# Adafruit_Trinket_3_3V.net
KiCad netlist of a schematic drawn in EAGLE
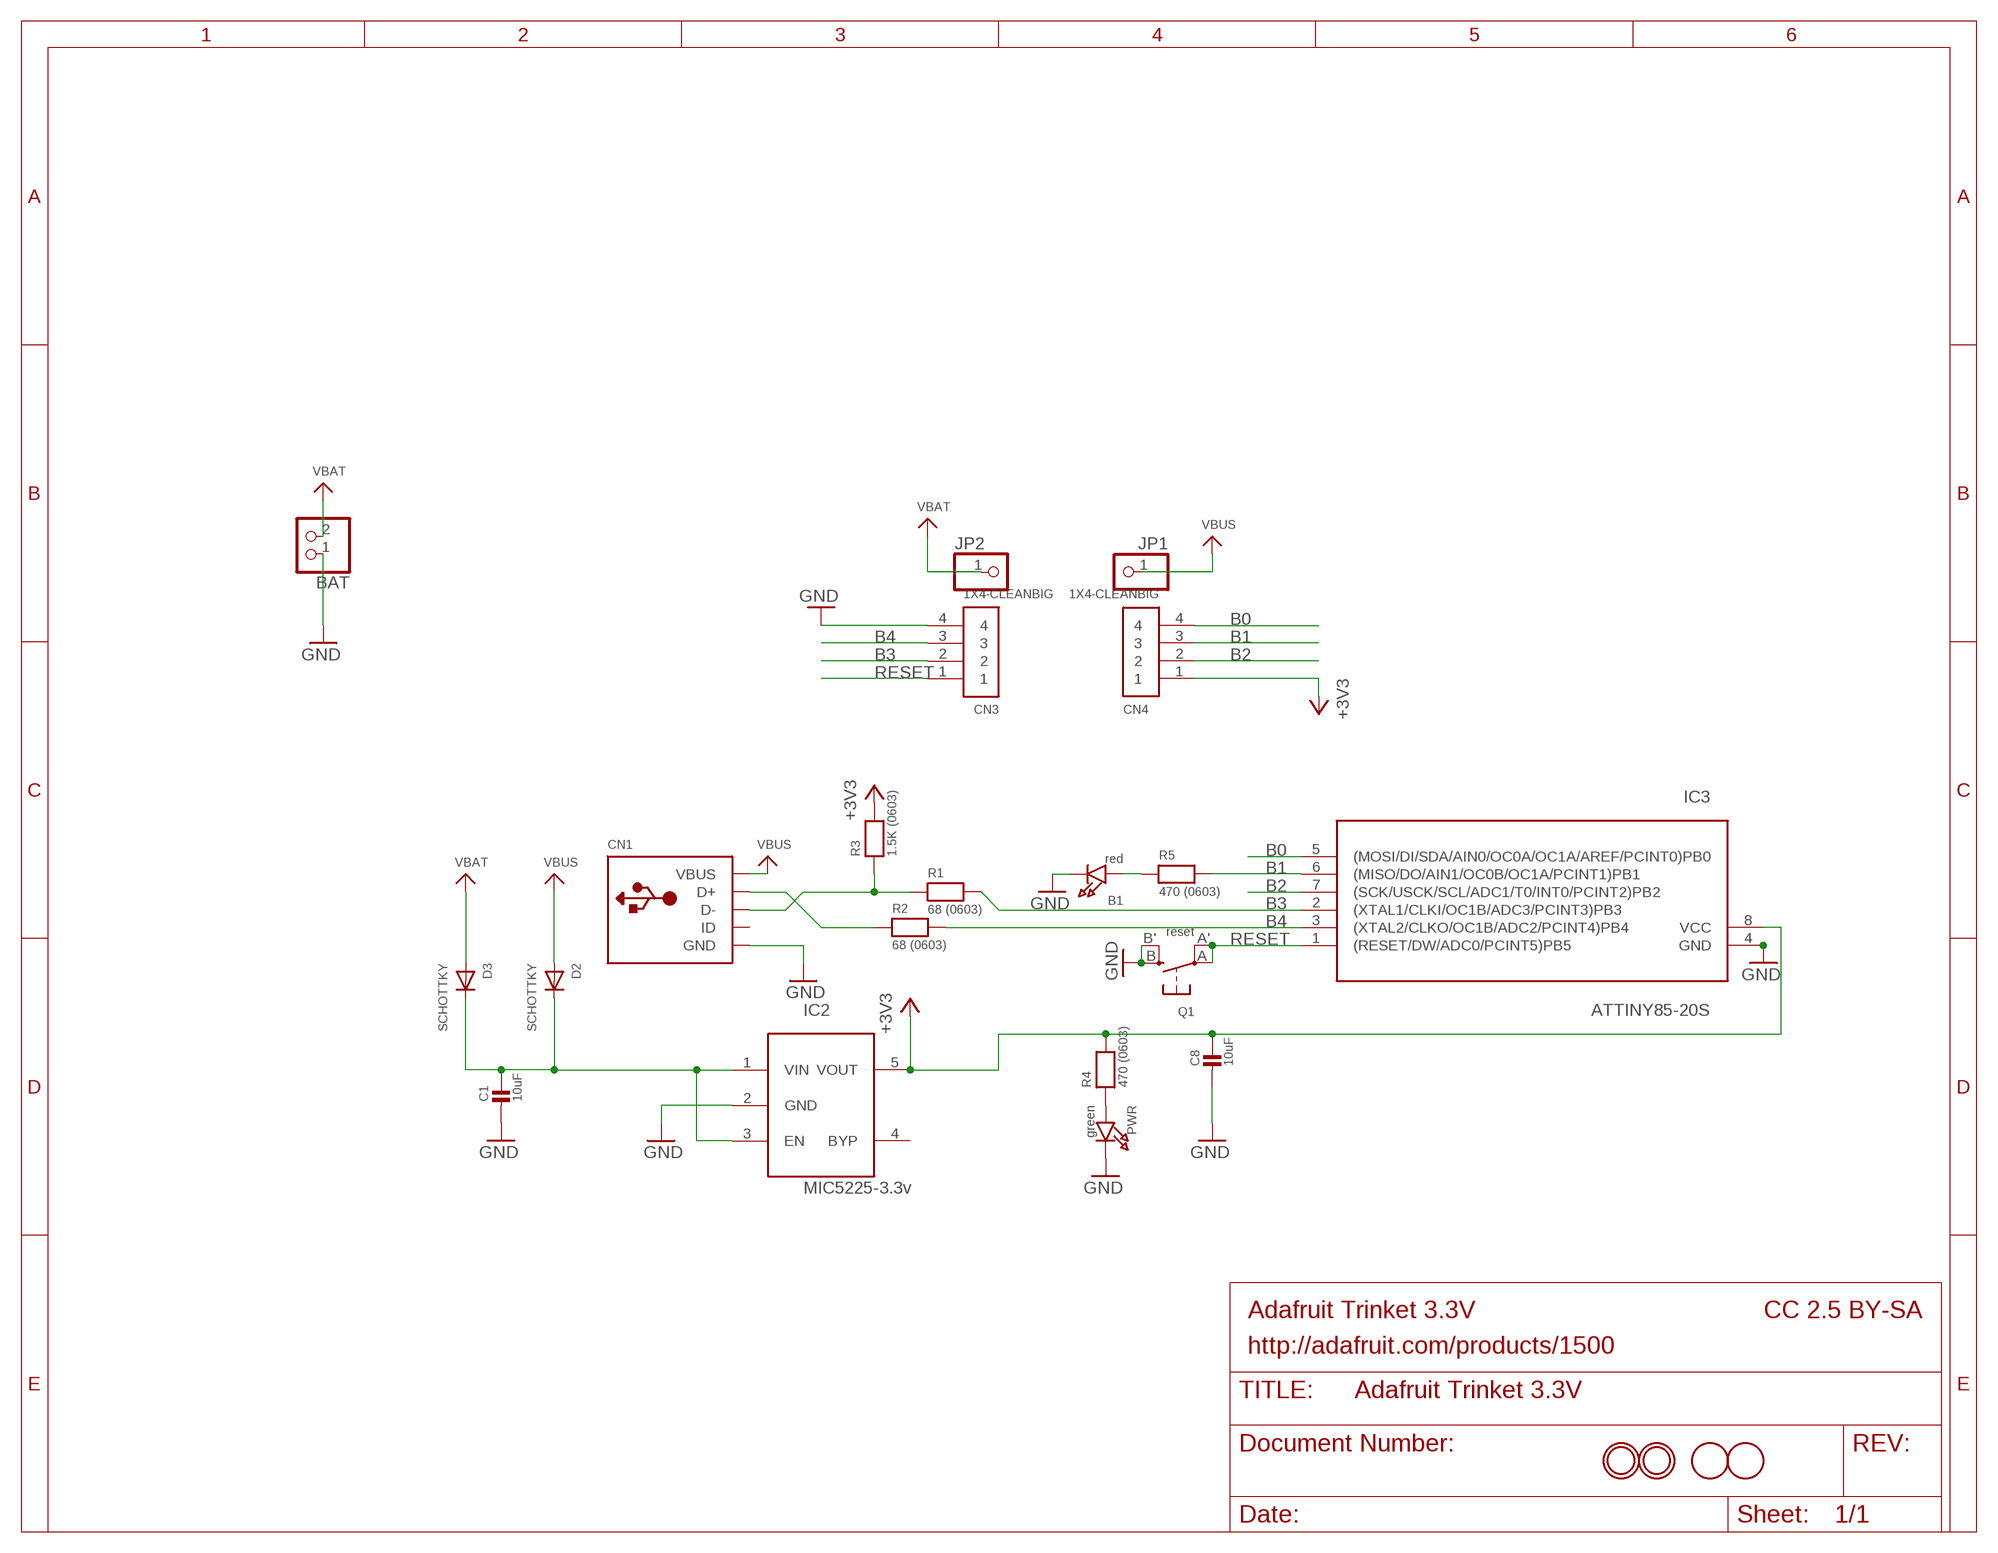
[diagram p0: schematic, sheet 1]

(export (version "E")
  (design (tool "Eeschema 10.0.6"))
  (components
    (comp (ref "B1")
      (value "red")
      (footprint "eagle-import:CHIPLED_0805_NOOUTLINE")
      (libsource (lib "eagle-import") (part "LED0805_NOOUTLINE"))
    )
    (comp (ref "BAT")
      (value "CON_JST_PH_2PIN")
      (footprint "eagle-import:JSTPH2")
      (libsource (lib "eagle-import") (part "CON_JST_PH_2PIN"))
    )
    (comp (ref "C1")
      (value "10uF")
      (footprint "eagle-import:0805-NO")
      (libsource (lib "eagle-import") (part "CAP_CERAMIC0805-NOOUTLINE"))
    )
    (comp (ref "C8")
      (value "10uF")
      (footprint "eagle-import:0805-NO")
      (libsource (lib "eagle-import") (part "CAP_CERAMIC0805-NOOUTLINE"))
    )
    (comp (ref "CN1")
      (value "USBMINIB")
      (footprint "eagle-import:USB-MINIB")
      (libsource (lib "eagle-import") (part "USBMINIB"))
    )
    (comp (ref "CN3")
      (value "1X4-CLEANBIG")
      (footprint "eagle-import:1X04-CLEANBIG")
      (libsource (lib "eagle-import") (part "1X4-CLEANBIG"))
    )
    (comp (ref "CN4")
      (value "1X4-CLEANBIG")
      (footprint "eagle-import:1X04-CLEANBIG")
      (libsource (lib "eagle-import") (part "1X4-CLEANBIG"))
    )
    (comp (ref "D2")
      (value "SCHOTTKY")
      (footprint "eagle-import:SOD-123FL")
      (libsource (lib "eagle-import") (part "DIODE_SOD-123FL"))
    )
    (comp (ref "D3")
      (value "SCHOTTKY")
      (footprint "eagle-import:SOD-123FL")
      (libsource (lib "eagle-import") (part "DIODE_SOD-123FL"))
    )
    (comp (ref "IC2")
      (value "MIC5225-3.3v")
      (footprint "eagle-import:SOT23-5L")
      (libsource (lib "eagle-import") (part "LP298XS"))
    )
    (comp (ref "IC3")
      (value "ATTINY85-20S")
      (footprint "eagle-import:SOIC8")
      (libsource (lib "eagle-import") (part "ATTINY85SV-10"))
    )
    (comp (ref "JP1")
      (value "PINHD-1X1CB")
      (footprint "eagle-import:1X01-CLEANBIG")
      (libsource (lib "eagle-import") (part "PINHD-1X1CB"))
    )
    (comp (ref "JP2")
      (value "PINHD-1X1CB")
      (footprint "eagle-import:1X01-CLEANBIG")
      (libsource (lib "eagle-import") (part "PINHD-1X1CB"))
    )
    (comp (ref "PWR")
      (value "green")
      (footprint "eagle-import:CHIPLED_0805_NOOUTLINE")
      (libsource (lib "eagle-import") (part "LED0805_NOOUTLINE"))
    )
    (comp (ref "Q1")
      (value "reset")
      (footprint "eagle-import:BTN_KMR2_4.6X2.8")
      (libsource (lib "eagle-import") (part "SWITCH_TACT_SMT4.6X2.8"))
    )
    (comp (ref "R1")
      (value "68 (0603)")
      (footprint "eagle-import:0603-NO")
      (libsource (lib "eagle-import") (part "RESISTOR_0603_NOOUT"))
    )
    (comp (ref "R2")
      (value "68 (0603)")
      (footprint "eagle-import:0603-NO")
      (libsource (lib "eagle-import") (part "RESISTOR_0603_NOOUT"))
    )
    (comp (ref "R3")
      (value "1.5K (0603)")
      (footprint "eagle-import:0603-NO")
      (libsource (lib "eagle-import") (part "RESISTOR_0603_NOOUT"))
    )
    (comp (ref "R4")
      (value "470 (0603)")
      (footprint "eagle-import:0603-NO")
      (libsource (lib "eagle-import") (part "RESISTOR_0603_NOOUT"))
    )
    (comp (ref "R5")
      (value "470 (0603)")
      (footprint "eagle-import:0603-NO")
      (libsource (lib "eagle-import") (part "RESISTOR_0603_NOOUT"))
    )
    (comp (ref "U$1")
      (value "FIDUCIAL")
      (footprint "eagle-import:FIDUCIAL_1MM")
      (libsource (lib "eagle-import") (part "FIDUCIAL"))
    )
    (comp (ref "U$6")
      (value "FIDUCIAL")
      (footprint "eagle-import:FIDUCIAL_1MM")
      (libsource (lib "eagle-import") (part "FIDUCIAL"))
    )
    (comp (ref "U$8")
      (value "MOUNTINGHOLE2.0")
      (footprint "eagle-import:MOUNTINGHOLE_2.0_PLATED")
      (libsource (lib "eagle-import") (part "MOUNTINGHOLE2.0"))
    )
    (comp (ref "U$9")
      (value "MOUNTINGHOLE2.0")
      (footprint "eagle-import:MOUNTINGHOLE_2.0_PLATED")
      (libsource (lib "eagle-import") (part "MOUNTINGHOLE2.0"))
    )
  )
  (nets
    (net (code "1") (name "+3V3") (class "Default")
      (node (ref "C8") (pin "1") (pinfunction "1_1") (pintype "passive"))
      (node (ref "CN4") (pin "1") (pinfunction "1_1") (pintype "bidirectional"))
      (node (ref "IC2") (pin "5") (pinfunction "VOUT_5") (pintype "bidirectional"))
      (node (ref "IC3") (pin "8") (pinfunction "VCC_8") (pintype "bidirectional"))
      (node (ref "R3") (pin "2") (pinfunction "2_2") (pintype "passive"))
      (node (ref "R4") (pin "2") (pinfunction "2_2") (pintype "passive"))
    )
    (net (code "2") (name "/B0") (class "Default")
      (node (ref "CN4") (pin "4") (pinfunction "4_4") (pintype "bidirectional"))
      (node (ref "IC3") (pin "5") (pinfunction "(MOSI/DI/SDA/AIN0/OC0A/OC1A/AREF/PCINT0)PB0_5") (pintype "bidirectional"))
    )
    (net (code "3") (name "/B1") (class "Default")
      (node (ref "CN4") (pin "3") (pinfunction "3_3") (pintype "bidirectional"))
      (node (ref "IC3") (pin "6") (pinfunction "(MISO/DO/AIN1/OC0B/OC1A/PCINT1)PB1_6") (pintype "bidirectional"))
      (node (ref "R5") (pin "2") (pinfunction "2_2") (pintype "passive"))
    )
    (net (code "4") (name "/B2") (class "Default")
      (node (ref "CN4") (pin "2") (pinfunction "2_2") (pintype "bidirectional"))
      (node (ref "IC3") (pin "7") (pinfunction "(SCK/USCK/SCL/ADC1/T0/INT0/PCINT2)PB2_7") (pintype "bidirectional"))
    )
    (net (code "5") (name "/B3") (class "Default")
      (node (ref "CN3") (pin "2") (pinfunction "2_2") (pintype "bidirectional"))
      (node (ref "IC3") (pin "2") (pinfunction "(XTAL1/CLKI/OC1B/ADC3/PCINT3)PB3_2") (pintype "bidirectional"))
      (node (ref "R1") (pin "2") (pinfunction "2_2") (pintype "passive"))
    )
    (net (code "6") (name "/B4") (class "Default")
      (node (ref "CN3") (pin "3") (pinfunction "3_3") (pintype "bidirectional"))
      (node (ref "IC3") (pin "3") (pinfunction "(XTAL2/CLKO/OC1B/ADC2/PCINT4)PB4_3") (pintype "bidirectional"))
      (node (ref "R2") (pin "2") (pinfunction "2_2") (pintype "passive"))
    )
    (net (code "7") (name "/RESET") (class "Default")
      (node (ref "CN3") (pin "1") (pinfunction "1_1") (pintype "bidirectional"))
      (node (ref "IC3") (pin "1") (pinfunction "(RESET/DW/ADC0/PCINT5)PB5_1") (pintype "bidirectional"))
      (node (ref "Q1") (pin "A") (pinfunction "P_A") (pintype "passive"))
      (node (ref "Q1") (pin "A'") (pinfunction "P1_A'") (pintype "passive"))
    )
    (net (code "8") (name "GND") (class "Default")
      (node (ref "B1") (pin "C") (pinfunction "C_C") (pintype "passive"))
      (node (ref "BAT") (pin "1") (pinfunction "1_1") (pintype "passive"))
      (node (ref "C1") (pin "2") (pinfunction "2_2") (pintype "passive"))
      (node (ref "C8") (pin "2") (pinfunction "2_2") (pintype "passive"))
      (node (ref "CN1") (pin "GND") (pinfunction "GND_GND") (pintype "power_in"))
      (node (ref "CN1") (pin "GND1") (pinfunction "GND_GND1") (pintype "power_in"))
      (node (ref "CN1") (pin "GND2") (pinfunction "GND_GND2") (pintype "power_in"))
      (node (ref "CN1") (pin "GND3") (pinfunction "GND_GND3") (pintype "power_in"))
      (node (ref "CN1") (pin "GND4") (pinfunction "GND_GND4") (pintype "power_in"))
      (node (ref "CN3") (pin "4") (pinfunction "4_4") (pintype "bidirectional"))
      (node (ref "IC2") (pin "2") (pinfunction "GND_2") (pintype "bidirectional"))
      (node (ref "IC3") (pin "4") (pinfunction "GND_4") (pintype "bidirectional"))
      (node (ref "PWR") (pin "C") (pinfunction "C_C") (pintype "passive"))
      (node (ref "Q1") (pin "B") (pinfunction "S_B") (pintype "passive"))
      (node (ref "Q1") (pin "B'") (pinfunction "S1_B'") (pintype "passive"))
    )
    (net (code "9") (name "Net-(B1-PadA)") (class "Default")
      (node (ref "B1") (pin "A") (pinfunction "A_A") (pintype "passive"))
      (node (ref "R5") (pin "1") (pinfunction "1_1") (pintype "passive"))
    )
    (net (code "10") (name "Net-(CN1-PadD+)") (class "Default")
      (node (ref "CN1") (pin "D+") (pinfunction "D+_D+") (pintype "bidirectional"))
      (node (ref "R2") (pin "1") (pinfunction "1_1") (pintype "passive"))
    )
    (net (code "11") (name "Net-(CN1-PadD-)") (class "Default")
      (node (ref "CN1") (pin "D-") (pinfunction "D-_D-") (pintype "bidirectional"))
      (node (ref "R1") (pin "1") (pinfunction "1_1") (pintype "passive"))
      (node (ref "R3") (pin "1") (pinfunction "1_1") (pintype "passive"))
    )
    (net (code "12") (name "Net-(IC2-EN)") (class "Default")
      (node (ref "C1") (pin "1") (pinfunction "1_1") (pintype "passive"))
      (node (ref "D2") (pin "C") (pinfunction "C_C") (pintype "passive"))
      (node (ref "D3") (pin "C") (pinfunction "C_C") (pintype "passive"))
      (node (ref "IC2") (pin "1") (pinfunction "VIN_1") (pintype "bidirectional"))
      (node (ref "IC2") (pin "3") (pinfunction "EN_3") (pintype "bidirectional"))
    )
    (net (code "13") (name "Net-(PWR-PadA)") (class "Default")
      (node (ref "PWR") (pin "A") (pinfunction "A_A") (pintype "passive"))
      (node (ref "R4") (pin "1") (pinfunction "1_1") (pintype "passive"))
    )
    (net (code "14") (name "VBAT") (class "Default")
      (node (ref "BAT") (pin "2") (pinfunction "2_2") (pintype "passive"))
      (node (ref "D3") (pin "A") (pinfunction "A_A") (pintype "passive"))
      (node (ref "JP2") (pin "1") (pinfunction "1_1") (pintype "passive"))
    )
    (net (code "15") (name "VBUS") (class "Default")
      (node (ref "CN1") (pin "VBUS") (pinfunction "VBUS_VBUS") (pintype "power_in"))
      (node (ref "D2") (pin "A") (pinfunction "A_A") (pintype "passive"))
      (node (ref "JP1") (pin "1") (pinfunction "1_1") (pintype "passive"))
    )
    (net (code "16") (name "unconnected-(CN1-PadID)") (class "Default")
      (node (ref "CN1") (pin "ID") (pinfunction "ID_ID") (pintype "bidirectional"))
    )
    (net (code "17") (name "unconnected-(IC2-BYP-Pad4)") (class "Default")
      (node (ref "IC2") (pin "4") (pinfunction "BYP_4") (pintype "bidirectional"))
    )
  )
)
